# Headers.net
KiCad netlist of a schematic drawn in Altium Designer
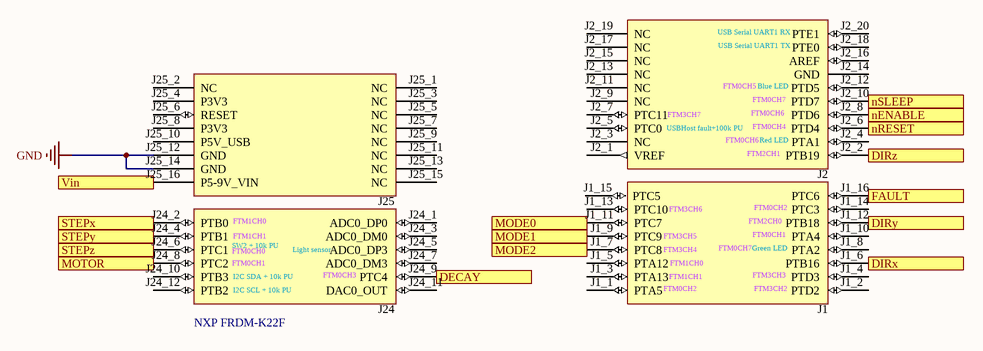
[diagram p0: Headers.SchDoc]

(export (version "E")
  (design (tool "Eeschema 10.0.6"))
  (components
    (comp (ref "*")
      (value "NXP FRDM-K22F")
      (footprint "FRDM-K22F")
      (libsource (lib "JCULibrary_AS2") (part "NXP FRDM-K22F"))
    )
  )
  (nets
    (net (code "1") (name "/DECAY") (class "Default")
      (node (ref "*") (pin "J24_9") (pinfunction "PTC4_J24_9") (pintype "bidirectional"))
    )
    (net (code "2") (name "/DIRx") (class "Default")
      (node (ref "*") (pin "J1_6") (pinfunction "PTB16_J1_6") (pintype "bidirectional"))
    )
    (net (code "3") (name "/DIRy") (class "Default")
      (node (ref "*") (pin "J1_12") (pinfunction "PTB18_J1_12") (pintype "bidirectional"))
    )
    (net (code "4") (name "/DIRz") (class "Default")
      (node (ref "*") (pin "J2_2") (pinfunction "PTB19_J2_2") (pintype "bidirectional"))
    )
    (net (code "5") (name "/FAULT") (class "Default")
      (node (ref "*") (pin "J1_16") (pinfunction "PTC6_J1_16") (pintype "bidirectional"))
    )
    (net (code "6") (name "/MODE0") (class "Default")
      (node (ref "*") (pin "J1_11") (pinfunction "PTC7_J1_11") (pintype "bidirectional"))
    )
    (net (code "7") (name "/MODE1") (class "Default")
      (node (ref "*") (pin "J1_9") (pinfunction "PTC9_J1_9") (pintype "bidirectional"))
    )
    (net (code "8") (name "/MODE2") (class "Default")
      (node (ref "*") (pin "J1_7") (pinfunction "PTC8_J1_7") (pintype "bidirectional"))
    )
    (net (code "9") (name "/MOTOR") (class "Default")
      (node (ref "*") (pin "J24_8") (pinfunction "PTC2_J24_8") (pintype "bidirectional"))
    )
    (net (code "10") (name "/STEPx") (class "Default")
      (node (ref "*") (pin "J24_2") (pinfunction "PTB0_J24_2") (pintype "bidirectional"))
    )
    (net (code "11") (name "/STEPy") (class "Default")
      (node (ref "*") (pin "J24_4") (pinfunction "PTB1_J24_4") (pintype "bidirectional"))
    )
    (net (code "12") (name "/STEPz") (class "Default")
      (node (ref "*") (pin "J24_6") (pinfunction "PTC1_J24_6") (pintype "bidirectional"))
    )
    (net (code "13") (name "/Vin") (class "Default")
      (node (ref "*") (pin "J25_16") (pinfunction "P5-9V_VIN_J25_16") (pintype "power_in"))
    )
    (net (code "14") (name "/nENABLE") (class "Default")
      (node (ref "*") (pin "J2_8") (pinfunction "PTD6_J2_8") (pintype "bidirectional"))
    )
    (net (code "15") (name "/nRESET") (class "Default")
      (node (ref "*") (pin "J2_6") (pinfunction "PTD4_J2_6") (pintype "bidirectional"))
    )
    (net (code "16") (name "/nSLEEP") (class "Default")
      (node (ref "*") (pin "J2_10") (pinfunction "PTD7_J2_10") (pintype "bidirectional"))
    )
    (net (code "17") (name "GND") (class "Default")
      (node (ref "*") (pin "J25_12") (pinfunction "GND_J25_12") (pintype "power_in"))
      (node (ref "*") (pin "J25_14") (pinfunction "GND_J25_14") (pintype "power_in"))
    )
    (net (code "18") (name "unconnected-(*-ADC0_DM0-PadJ24_3)") (class "Default")
      (node (ref "*") (pin "J24_3") (pinfunction "ADC0_DM0_J24_3") (pintype "bidirectional"))
    )
    (net (code "19") (name "unconnected-(*-ADC0_DM3-PadJ24_7)") (class "Default")
      (node (ref "*") (pin "J24_7") (pinfunction "ADC0_DM3_J24_7") (pintype "bidirectional"))
    )
    (net (code "20") (name "unconnected-(*-ADC0_DP0-PadJ24_1)") (class "Default")
      (node (ref "*") (pin "J24_1") (pinfunction "ADC0_DP0_J24_1") (pintype "bidirectional"))
    )
    (net (code "21") (name "unconnected-(*-ADC0_DP3-PadJ24_5)") (class "Default")
      (node (ref "*") (pin "J24_5") (pinfunction "ADC0_DP3_J24_5") (pintype "bidirectional"))
    )
    (net (code "22") (name "unconnected-(*-AREF-PadJ2_16)") (class "Default")
      (node (ref "*") (pin "J2_16") (pinfunction "AREF_J2_16") (pintype "bidirectional"))
    )
    (net (code "23") (name "unconnected-(*-DAC0_OUT-PadJ24_11)") (class "Default")
      (node (ref "*") (pin "J24_11") (pinfunction "DAC0_OUT_J24_11") (pintype "bidirectional"))
    )
    (net (code "24") (name "unconnected-(*-GND-PadJ2_14)") (class "Default")
      (node (ref "*") (pin "J2_14") (pinfunction "GND_J2_14") (pintype "power_in"))
    )
    (net (code "25") (name "unconnected-(*-NC-PadJ2_3)") (class "Default")
      (node (ref "*") (pin "J2_3") (pinfunction "NC_J2_3") (pintype "passive"))
    )
    (net (code "26") (name "unconnected-(*-NC-PadJ2_9)") (class "Default")
      (node (ref "*") (pin "J2_9") (pinfunction "NC_J2_9") (pintype "passive"))
    )
    (net (code "27") (name "unconnected-(*-NC-PadJ2_11)") (class "Default")
      (node (ref "*") (pin "J2_11") (pinfunction "NC_J2_11") (pintype "passive"))
    )
    (net (code "28") (name "unconnected-(*-NC-PadJ2_13)") (class "Default")
      (node (ref "*") (pin "J2_13") (pinfunction "NC_J2_13") (pintype "passive"))
    )
    (net (code "29") (name "unconnected-(*-NC-PadJ2_15)") (class "Default")
      (node (ref "*") (pin "J2_15") (pinfunction "NC_J2_15") (pintype "passive"))
    )
    (net (code "30") (name "unconnected-(*-NC-PadJ2_17)") (class "Default")
      (node (ref "*") (pin "J2_17") (pinfunction "NC_J2_17") (pintype "passive"))
    )
    (net (code "31") (name "unconnected-(*-NC-PadJ2_19)") (class "Default")
      (node (ref "*") (pin "J2_19") (pinfunction "NC_J2_19") (pintype "passive"))
    )
    (net (code "32") (name "unconnected-(*-NC-PadJ25_1)") (class "Default")
      (node (ref "*") (pin "J25_1") (pinfunction "NC_J25_1") (pintype "passive"))
    )
    (net (code "33") (name "unconnected-(*-NC-PadJ25_2)") (class "Default")
      (node (ref "*") (pin "J25_2") (pinfunction "NC_J25_2") (pintype "passive"))
    )
    (net (code "34") (name "unconnected-(*-NC-PadJ25_3)") (class "Default")
      (node (ref "*") (pin "J25_3") (pinfunction "NC_J25_3") (pintype "passive"))
    )
    (net (code "35") (name "unconnected-(*-NC-PadJ25_5)") (class "Default")
      (node (ref "*") (pin "J25_5") (pinfunction "NC_J25_5") (pintype "passive"))
    )
    (net (code "36") (name "unconnected-(*-NC-PadJ25_7)") (class "Default")
      (node (ref "*") (pin "J25_7") (pinfunction "NC_J25_7") (pintype "passive"))
    )
    (net (code "37") (name "unconnected-(*-NC-PadJ25_9)") (class "Default")
      (node (ref "*") (pin "J25_9") (pinfunction "NC_J25_9") (pintype "passive"))
    )
    (net (code "38") (name "unconnected-(*-NC-PadJ25_11)") (class "Default")
      (node (ref "*") (pin "J25_11") (pinfunction "NC_J25_11") (pintype "passive"))
    )
    (net (code "39") (name "unconnected-(*-NC-PadJ25_13)") (class "Default")
      (node (ref "*") (pin "J25_13") (pinfunction "NC_J25_13") (pintype "passive"))
    )
    (net (code "40") (name "unconnected-(*-NC-PadJ25_15)") (class "Default")
      (node (ref "*") (pin "J25_15") (pinfunction "NC_J25_15") (pintype "passive"))
    )
    (net (code "41") (name "unconnected-(*-P3V3-PadJ25_4)") (class "Default")
      (node (ref "*") (pin "J25_4") (pinfunction "P3V3_J25_4") (pintype "power_in"))
    )
    (net (code "42") (name "unconnected-(*-P3V3-PadJ25_8)") (class "Default")
      (node (ref "*") (pin "J25_8") (pinfunction "P3V3_J25_8") (pintype "power_in"))
    )
    (net (code "43") (name "unconnected-(*-P5V_USB-PadJ25_10)") (class "Default")
      (node (ref "*") (pin "J25_10") (pinfunction "P5V_USB_J25_10") (pintype "power_in"))
    )
    (net (code "44") (name "unconnected-(*-PTA1-PadJ2_4)") (class "Default")
      (node (ref "*") (pin "J2_4") (pinfunction "PTA1_J2_4") (pintype "bidirectional"))
    )
    (net (code "45") (name "unconnected-(*-PTA2-PadJ1_8)") (class "Default")
      (node (ref "*") (pin "J1_8") (pinfunction "PTA2_J1_8") (pintype "bidirectional"))
    )
    (net (code "46") (name "unconnected-(*-PTA4-PadJ1_10)") (class "Default")
      (node (ref "*") (pin "J1_10") (pinfunction "PTA4_J1_10") (pintype "bidirectional"))
    )
    (net (code "47") (name "unconnected-(*-PTA5-PadJ1_1)") (class "Default")
      (node (ref "*") (pin "J1_1") (pinfunction "PTA5_J1_1") (pintype "bidirectional"))
    )
    (net (code "48") (name "unconnected-(*-PTA12-PadJ1_5)") (class "Default")
      (node (ref "*") (pin "J1_5") (pinfunction "PTA12_J1_5") (pintype "bidirectional"))
    )
    (net (code "49") (name "unconnected-(*-PTA13-PadJ1_3)") (class "Default")
      (node (ref "*") (pin "J1_3") (pinfunction "PTA13_J1_3") (pintype "bidirectional"))
    )
    (net (code "50") (name "unconnected-(*-PTB2-PadJ24_12)") (class "Default")
      (node (ref "*") (pin "J24_12") (pinfunction "PTB2_J24_12") (pintype "bidirectional"))
    )
    (net (code "51") (name "unconnected-(*-PTB3-PadJ24_10)") (class "Default")
      (node (ref "*") (pin "J24_10") (pinfunction "PTB3_J24_10") (pintype "bidirectional"))
    )
    (net (code "52") (name "unconnected-(*-PTC0-PadJ2_5)") (class "Default")
      (node (ref "*") (pin "J2_5") (pinfunction "PTC0_J2_5") (pintype "bidirectional"))
    )
    (net (code "53") (name "unconnected-(*-PTC3-PadJ1_14)") (class "Default")
      (node (ref "*") (pin "J1_14") (pinfunction "PTC3_J1_14") (pintype "bidirectional"))
    )
    (net (code "54") (name "unconnected-(*-PTC5-PadJ1_15)") (class "Default")
      (node (ref "*") (pin "J1_15") (pinfunction "PTC5_J1_15") (pintype "bidirectional"))
    )
    (net (code "55") (name "unconnected-(*-PTC10-PadJ1_13)") (class "Default")
      (node (ref "*") (pin "J1_13") (pinfunction "PTC10_J1_13") (pintype "bidirectional"))
    )
    (net (code "56") (name "unconnected-(*-PTC11-PadJ2_7)") (class "Default")
      (node (ref "*") (pin "J2_7") (pinfunction "PTC11_J2_7") (pintype "bidirectional"))
    )
    (net (code "57") (name "unconnected-(*-PTD2-PadJ1_2)") (class "Default")
      (node (ref "*") (pin "J1_2") (pinfunction "PTD2_J1_2") (pintype "bidirectional"))
    )
    (net (code "58") (name "unconnected-(*-PTD3-PadJ1_4)") (class "Default")
      (node (ref "*") (pin "J1_4") (pinfunction "PTD3_J1_4") (pintype "bidirectional"))
    )
    (net (code "59") (name "unconnected-(*-PTD5-PadJ2_12)") (class "Default")
      (node (ref "*") (pin "J2_12") (pinfunction "PTD5_J2_12") (pintype "bidirectional"))
    )
    (net (code "60") (name "unconnected-(*-PTE0-PadJ2_18)") (class "Default")
      (node (ref "*") (pin "J2_18") (pinfunction "PTE0_J2_18") (pintype "bidirectional"))
    )
    (net (code "61") (name "unconnected-(*-PTE1-PadJ2_20)") (class "Default")
      (node (ref "*") (pin "J2_20") (pinfunction "PTE1_J2_20") (pintype "bidirectional"))
    )
    (net (code "62") (name "unconnected-(*-RESET-PadJ25_6)") (class "Default")
      (node (ref "*") (pin "J25_6") (pinfunction "RESET_J25_6") (pintype "bidirectional"))
    )
    (net (code "63") (name "unconnected-(*-VREF-PadJ2_1)") (class "Default")
      (node (ref "*") (pin "J2_1") (pinfunction "VREF_J2_1") (pintype "output"))
    )
  )
)
